# 01_Power_IN.net
KiCad netlist of a schematic drawn in Altium Designer
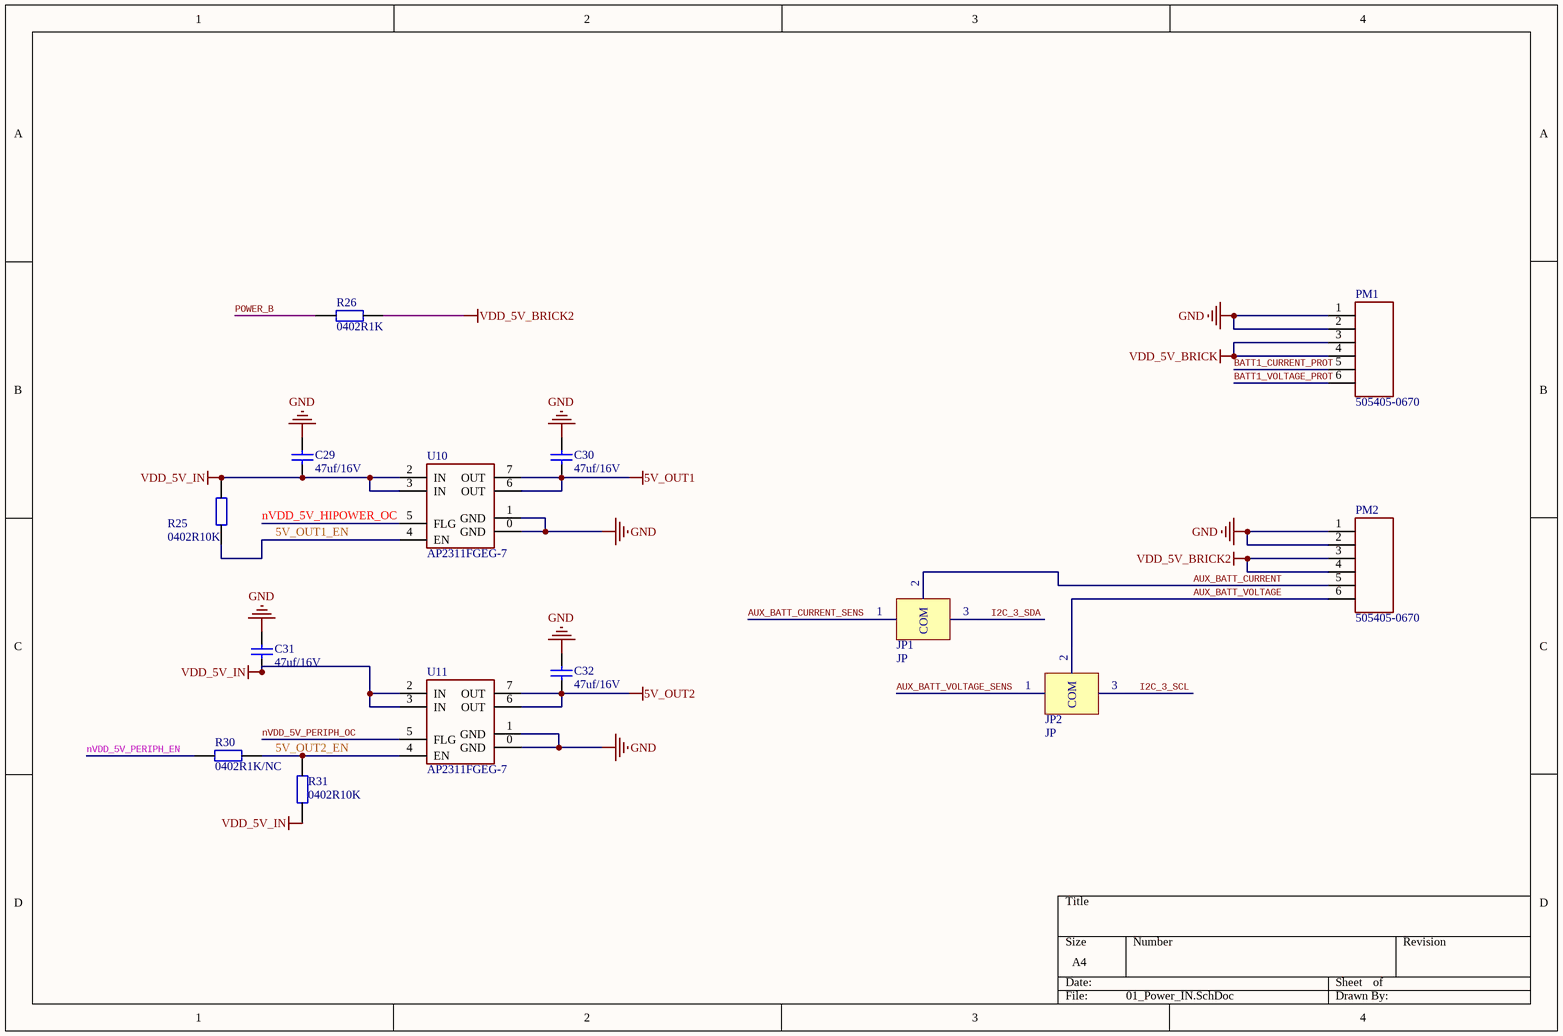
[diagram p0: 01_Power_IN.SchDoc]

(export (version "E")
  (design (tool "Eeschema 10.0.6"))
  (components
    (comp (ref "C29")
      (value "47uf/16V")
      (description "Capacitor")
      (libsource (lib "Miscellaneous Devices") (part "Cap"))
    )
    (comp (ref "C30")
      (value "47uf/16V")
      (description "Capacitor")
      (libsource (lib "Miscellaneous Devices") (part "Cap"))
    )
    (comp (ref "C31")
      (value "47uf/16V")
      (description "Capacitor")
      (libsource (lib "Miscellaneous Devices") (part "Cap"))
    )
    (comp (ref "C32")
      (value "47uf/16V")
      (description "Capacitor")
      (libsource (lib "Miscellaneous Devices") (part "Cap"))
    )
    (comp (ref "JP1") (value "JP") (footprint "0402R-SR") (libsource (lib "CUAV") (part "0402R-SR")))
    (comp (ref "JP2") (value "JP") (footprint "0402R-SR") (libsource (lib "CUAV") (part "0402R-SR")))
    (comp (ref "PM1")
      (value "505405-0670")
      (footprint "5054050660")
      (libsource (lib "CUAV") (part "5054050660"))
    )
    (comp (ref "PM2")
      (value "505405-0670")
      (footprint "5054050660")
      (libsource (lib "CUAV") (part "5054050660"))
    )
    (comp (ref "R25")
      (value "0402R10K")
      (footprint "0402R")
      (description "0402R1K 1%")
      (libsource (lib "") (part "0402R1K_1"))
    )
    (comp (ref "R26")
      (value "0402R1K")
      (footprint "0402R")
      (description "0402R1K 1%")
      (libsource (lib "") (part "0402R1K_2"))
    )
    (comp (ref "R30")
      (value "0402R1K/NC")
      (footprint "0402R")
      (description "0402R1K 1%")
      (libsource (lib "") (part "0402R1K_3"))
    )
    (comp (ref "R31")
      (value "0402R10K")
      (footprint "0402R")
      (description "0402R1K 1%")
      (libsource (lib "CUAV") (part "0402R1K"))
    )
    (comp (ref "U10")
      (value "AP2311FGEG-7")
      (footprint "QFN8_0.65")
      (libsource (lib "CUAV") (part "AP2311FGEG-7"))
    )
    (comp (ref "U11")
      (value "AP2311FGEG-7")
      (footprint "QFN8_0.65")
      (libsource (lib "CUAV") (part "AP2311FGEG-7"))
    )
  )
  (nets
    (net (code "1") (name "/5V_OUT1_EN") (class "Default")
      (node (ref "R25") (pin "1") (pintype "passive"))
      (node (ref "U10") (pin "4") (pinfunction "EN_4") (pintype "passive"))
    )
    (net (code "2") (name "/5V_OUT2_EN") (class "Default")
      (node (ref "R30") (pin "1") (pintype "passive"))
      (node (ref "R31") (pin "1") (pintype "passive"))
      (node (ref "U11") (pin "4") (pinfunction "EN_4") (pintype "passive"))
    )
    (net (code "3") (name "/AUX_BATT_CURRENT") (class "Default")
      (node (ref "JP1") (pin "2") (pinfunction "COM_2") (pintype "passive"))
      (node (ref "PM2") (pin "5") (pintype "passive"))
    )
    (net (code "4") (name "/AUX_BATT_CURRENT_SENS") (class "Default")
      (node (ref "JP1") (pin "1") (pintype "passive"))
    )
    (net (code "5") (name "/AUX_BATT_VOLTAGE") (class "Default")
      (node (ref "JP2") (pin "2") (pinfunction "COM_2") (pintype "passive"))
      (node (ref "PM2") (pin "6") (pintype "passive"))
    )
    (net (code "6") (name "/AUX_BATT_VOLTAGE_SENS") (class "Default")
      (node (ref "JP2") (pin "1") (pintype "passive"))
    )
    (net (code "7") (name "/BATT1_CURRENT_PROT") (class "Default")
      (node (ref "PM1") (pin "5") (pintype "passive"))
    )
    (net (code "8") (name "/BATT1_VOLTAGE_PROT") (class "Default")
      (node (ref "PM1") (pin "6") (pintype "passive"))
    )
    (net (code "9") (name "/I2C_3_SCL") (class "Default") (node (ref "JP2") (pin "3") (pintype "passive")))
    (net (code "10") (name "/I2C_3_SDA") (class "Default") (node (ref "JP1") (pin "3") (pintype "passive")))
    (net (code "11") (name "/POWER_B") (class "Default") (node (ref "R26") (pin "1") (pintype "passive")))
    (net (code "12") (name "/nVDD_5V_HIPOWER_OC") (class "Default")
      (node (ref "U10") (pin "5") (pinfunction "FLG_5") (pintype "passive"))
    )
    (net (code "13") (name "/nVDD_5V_PERIPH_EN") (class "Default")
      (node (ref "R30") (pin "2") (pintype "passive"))
    )
    (net (code "14") (name "/nVDD_5V_PERIPH_OC") (class "Default")
      (node (ref "U11") (pin "5") (pinfunction "FLG_5") (pintype "passive"))
    )
    (net (code "15") (name "5V_OUT1") (class "Default")
      (node (ref "C30") (pin "1") (pinfunction "1_1") (pintype "passive"))
      (node (ref "U10") (pin "6") (pinfunction "OUT_6") (pintype "passive"))
      (node (ref "U10") (pin "7") (pinfunction "OUT_7") (pintype "passive"))
    )
    (net (code "16") (name "5V_OUT2") (class "Default")
      (node (ref "C32") (pin "1") (pinfunction "1_1") (pintype "passive"))
      (node (ref "U11") (pin "6") (pinfunction "OUT_6") (pintype "passive"))
      (node (ref "U11") (pin "7") (pinfunction "OUT_7") (pintype "passive"))
    )
    (net (code "17") (name "GND") (class "Default")
      (node (ref "C29") (pin "2") (pinfunction "2_2") (pintype "passive"))
      (node (ref "C30") (pin "2") (pinfunction "2_2") (pintype "passive"))
      (node (ref "C31") (pin "2") (pinfunction "2_2") (pintype "passive"))
      (node (ref "C32") (pin "2") (pinfunction "2_2") (pintype "passive"))
      (node (ref "PM1") (pin "1") (pintype "passive"))
      (node (ref "PM1") (pin "2") (pintype "passive"))
      (node (ref "PM2") (pin "1") (pintype "passive"))
      (node (ref "PM2") (pin "2") (pintype "passive"))
      (node (ref "U10") (pin "0") (pinfunction "GND_0") (pintype "passive"))
      (node (ref "U10") (pin "1") (pinfunction "GND_1") (pintype "passive"))
      (node (ref "U11") (pin "0") (pinfunction "GND_0") (pintype "passive"))
      (node (ref "U11") (pin "1") (pinfunction "GND_1") (pintype "passive"))
    )
    (net (code "18") (name "VDD_5V_BRICK") (class "Default")
      (node (ref "PM1") (pin "3") (pintype "passive"))
      (node (ref "PM1") (pin "4") (pintype "passive"))
    )
    (net (code "19") (name "VDD_5V_BRICK2") (class "Default")
      (node (ref "PM2") (pin "3") (pintype "passive"))
      (node (ref "PM2") (pin "4") (pintype "passive"))
      (node (ref "R26") (pin "2") (pintype "passive"))
    )
    (net (code "20") (name "VDD_5V_IN") (class "Default")
      (node (ref "C29") (pin "1") (pinfunction "1_1") (pintype "passive"))
      (node (ref "C31") (pin "1") (pinfunction "1_1") (pintype "passive"))
      (node (ref "R25") (pin "2") (pintype "passive"))
      (node (ref "R31") (pin "2") (pintype "passive"))
      (node (ref "U10") (pin "2") (pinfunction "IN_2") (pintype "passive"))
      (node (ref "U10") (pin "3") (pinfunction "IN_3") (pintype "passive"))
      (node (ref "U11") (pin "2") (pinfunction "IN_2") (pintype "passive"))
      (node (ref "U11") (pin "3") (pinfunction "IN_3") (pintype "passive"))
    )
  )
)
